# Wifi_Board.net
KiCad netlist of a schematic drawn in EAGLE
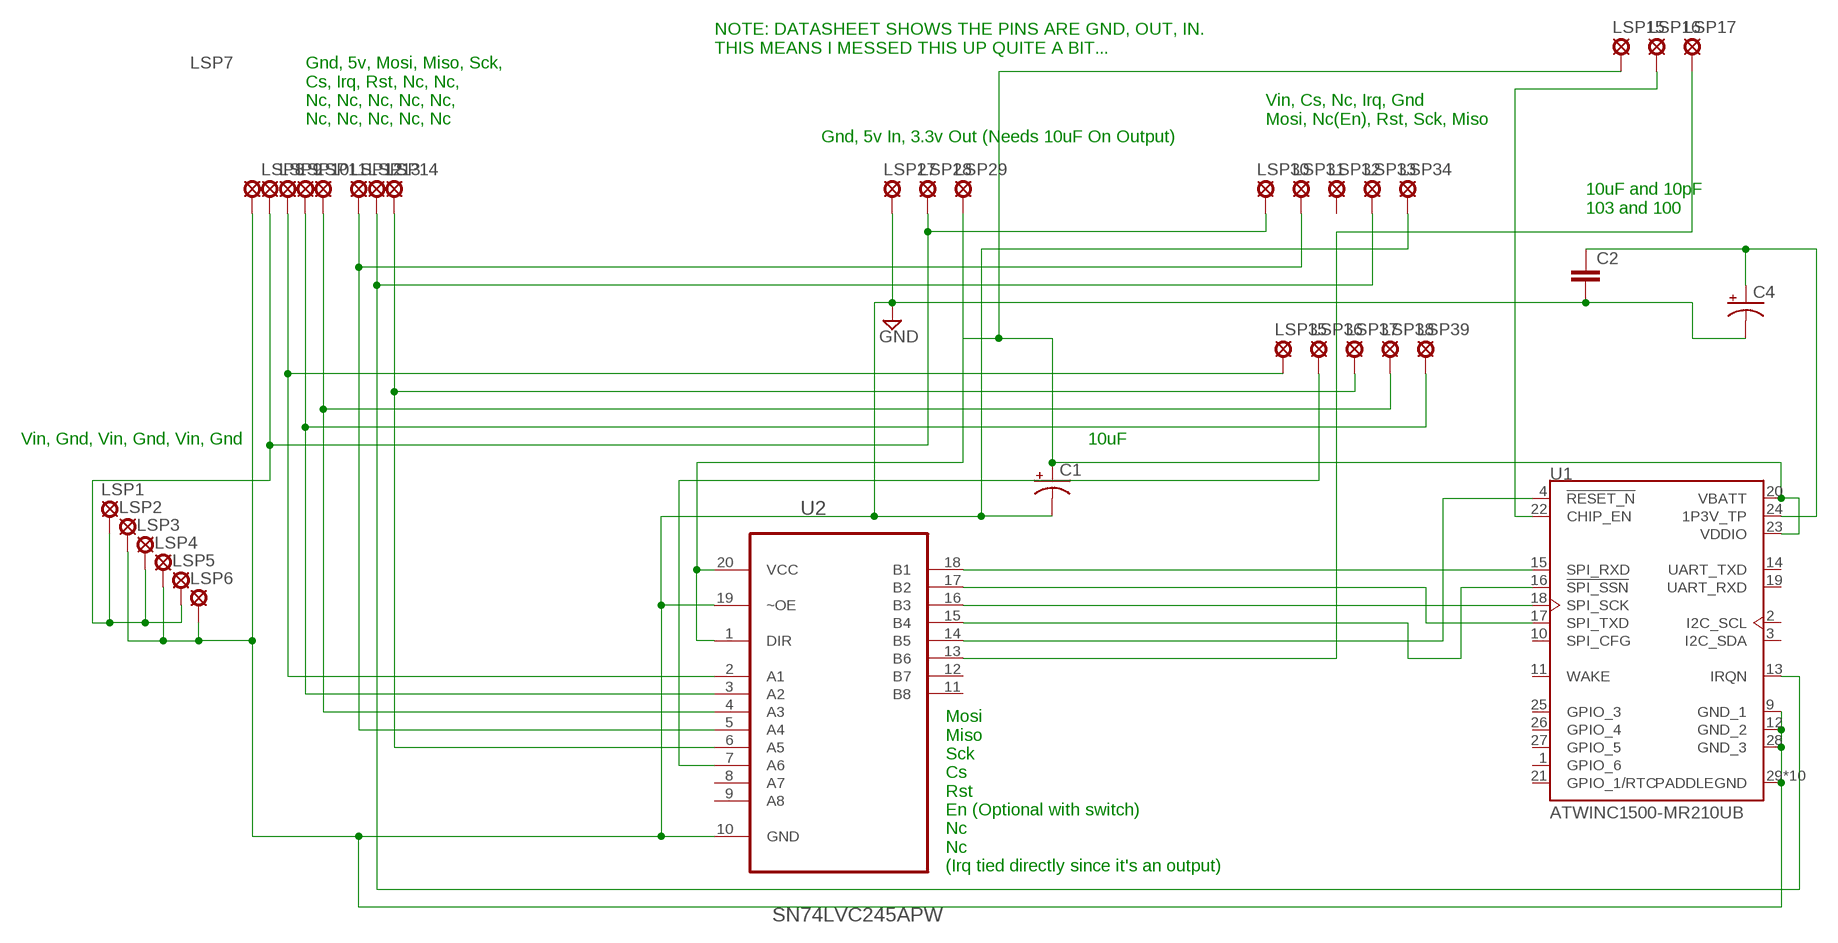
[diagram p0: schematic, sheet 1]

(export (version "E")
  (design (tool "Eeschema 10.0.6"))
  (components
    (comp (ref "C1")
      (value "CPOL-USE2-4")
      (footprint "eagle-import:E2-4")
      (libsource (lib "eagle-import") (part "CPOL-USE2-4"))
    )
    (comp (ref "C2")
      (value "C5/2.5")
      (footprint "eagle-import:C5B2.5")
      (libsource (lib "eagle-import") (part "C5/2.5"))
    )
    (comp (ref "C4")
      (value "CPOL-USE2-4")
      (footprint "eagle-import:E2-4")
      (libsource (lib "eagle-import") (part "CPOL-USE2-4"))
    )
    (comp (ref "LSP1")
      (value "LSP10_CLSP10_C")
      (footprint "eagle-import:LSP10_C")
      (libsource (lib "eagle-import") (part "LSP10_CLSP10_C"))
    )
    (comp (ref "LSP2")
      (value "LSP10_CLSP10_C")
      (footprint "eagle-import:LSP10_C")
      (libsource (lib "eagle-import") (part "LSP10_CLSP10_C"))
    )
    (comp (ref "LSP3")
      (value "LSP10_CLSP10_C")
      (footprint "eagle-import:LSP10_C")
      (libsource (lib "eagle-import") (part "LSP10_CLSP10_C"))
    )
    (comp (ref "LSP4")
      (value "LSP10_CLSP10_C")
      (footprint "eagle-import:LSP10_C")
      (libsource (lib "eagle-import") (part "LSP10_CLSP10_C"))
    )
    (comp (ref "LSP5")
      (value "LSP10_CLSP10_C")
      (footprint "eagle-import:LSP10_C")
      (libsource (lib "eagle-import") (part "LSP10_CLSP10_C"))
    )
    (comp (ref "LSP6")
      (value "LSP10_CLSP10_C")
      (footprint "eagle-import:LSP10_C")
      (libsource (lib "eagle-import") (part "LSP10_CLSP10_C"))
    )
    (comp (ref "LSP7")
      (value "LSP10_CLSP10_C")
      (footprint "eagle-import:LSP10_C")
      (libsource (lib "eagle-import") (part "LSP10_CLSP10_C"))
    )
    (comp (ref "LSP8")
      (value "LSP10_CLSP10_C")
      (footprint "eagle-import:LSP10_C")
      (libsource (lib "eagle-import") (part "LSP10_CLSP10_C"))
    )
    (comp (ref "LSP9")
      (value "LSP10_CLSP10_C")
      (footprint "eagle-import:LSP10_C")
      (libsource (lib "eagle-import") (part "LSP10_CLSP10_C"))
    )
    (comp (ref "LSP10")
      (value "LSP10_CLSP10_C")
      (footprint "eagle-import:LSP10_C")
      (libsource (lib "eagle-import") (part "LSP10_CLSP10_C"))
    )
    (comp (ref "LSP11")
      (value "LSP10_CLSP10_C")
      (footprint "eagle-import:LSP10_C")
      (libsource (lib "eagle-import") (part "LSP10_CLSP10_C"))
    )
    (comp (ref "LSP12")
      (value "LSP10_CLSP10_C")
      (footprint "eagle-import:LSP10_C")
      (libsource (lib "eagle-import") (part "LSP10_CLSP10_C"))
    )
    (comp (ref "LSP13")
      (value "LSP10_CLSP10_C")
      (footprint "eagle-import:LSP10_C")
      (libsource (lib "eagle-import") (part "LSP10_CLSP10_C"))
    )
    (comp (ref "LSP14")
      (value "LSP10_CLSP10_C")
      (footprint "eagle-import:LSP10_C")
      (libsource (lib "eagle-import") (part "LSP10_CLSP10_C"))
    )
    (comp (ref "LSP15")
      (value "LSP10_CLSP10_C")
      (footprint "eagle-import:LSP10_C")
      (libsource (lib "eagle-import") (part "LSP10_CLSP10_C"))
    )
    (comp (ref "LSP16")
      (value "LSP10_CLSP10_C")
      (footprint "eagle-import:LSP10_C")
      (libsource (lib "eagle-import") (part "LSP10_CLSP10_C"))
    )
    (comp (ref "LSP17")
      (value "LSP10_CLSP10_C")
      (footprint "eagle-import:LSP10_C")
      (libsource (lib "eagle-import") (part "LSP10_CLSP10_C"))
    )
    (comp (ref "LSP27")
      (value "LSP10_CLSP10_C")
      (footprint "eagle-import:LSP10_C")
      (libsource (lib "eagle-import") (part "LSP10_CLSP10_C"))
    )
    (comp (ref "LSP28")
      (value "LSP10_CLSP10_C")
      (footprint "eagle-import:LSP10_C")
      (libsource (lib "eagle-import") (part "LSP10_CLSP10_C"))
    )
    (comp (ref "LSP29")
      (value "LSP10_CLSP10_C")
      (footprint "eagle-import:LSP10_C")
      (libsource (lib "eagle-import") (part "LSP10_CLSP10_C"))
    )
    (comp (ref "LSP30")
      (value "LSP10_CLSP10_C")
      (footprint "eagle-import:LSP10_C")
      (libsource (lib "eagle-import") (part "LSP10_CLSP10_C"))
    )
    (comp (ref "LSP31")
      (value "LSP10_CLSP10_C")
      (footprint "eagle-import:LSP10_C")
      (libsource (lib "eagle-import") (part "LSP10_CLSP10_C"))
    )
    (comp (ref "LSP32")
      (value "LSP10_CLSP10_C")
      (footprint "eagle-import:LSP10_C")
      (libsource (lib "eagle-import") (part "LSP10_CLSP10_C"))
    )
    (comp (ref "LSP33")
      (value "LSP10_CLSP10_C")
      (footprint "eagle-import:LSP10_C")
      (libsource (lib "eagle-import") (part "LSP10_CLSP10_C"))
    )
    (comp (ref "LSP34")
      (value "LSP10_CLSP10_C")
      (footprint "eagle-import:LSP10_C")
      (libsource (lib "eagle-import") (part "LSP10_CLSP10_C"))
    )
    (comp (ref "LSP35")
      (value "LSP10_CLSP10_C")
      (footprint "eagle-import:LSP10_C")
      (libsource (lib "eagle-import") (part "LSP10_CLSP10_C"))
    )
    (comp (ref "LSP36")
      (value "LSP10_CLSP10_C")
      (footprint "eagle-import:LSP10_C")
      (libsource (lib "eagle-import") (part "LSP10_CLSP10_C"))
    )
    (comp (ref "LSP37")
      (value "LSP10_CLSP10_C")
      (footprint "eagle-import:LSP10_C")
      (libsource (lib "eagle-import") (part "LSP10_CLSP10_C"))
    )
    (comp (ref "LSP38")
      (value "LSP10_CLSP10_C")
      (footprint "eagle-import:LSP10_C")
      (libsource (lib "eagle-import") (part "LSP10_CLSP10_C"))
    )
    (comp (ref "LSP39")
      (value "LSP10_CLSP10_C")
      (footprint "eagle-import:LSP10_C")
      (libsource (lib "eagle-import") (part "LSP10_CLSP10_C"))
    )
    (comp (ref "U1")
      (value "ATWINC1500-MR210UB")
      (footprint "eagle-import:MICROCHIP_ATWINC1500-MR210UB")
      (fields (field (name "MF") "Microchip"))
      (libsource (lib "eagle-import") (part "ATWINC1500-MR210UB"))
    )
    (comp (ref "U2")
      (value "SN74LVC245APW")
      (footprint "eagle-import:SOP65P640X120-20N")
      (fields (field (name "MF") "Texas Instruments"))
      (libsource (lib "eagle-import") (part "SN74LVC245APW"))
    )
  )
  (nets
    (net (code "1") (name "GND") (class "Default")
      (node (ref "C1") (pin "-") (pinfunction "-_-") (pintype "passive"))
      (node (ref "C2") (pin "2") (pinfunction "2_2") (pintype "passive"))
      (node (ref "C4") (pin "-") (pinfunction "-_-") (pintype "passive"))
      (node (ref "LSP2") (pin "P$1") (pinfunction "MP_P$1") (pintype "passive"))
      (node (ref "LSP27") (pin "P$1") (pinfunction "MP_P$1") (pintype "passive"))
      (node (ref "LSP34") (pin "P$1") (pinfunction "MP_P$1") (pintype "passive"))
      (node (ref "LSP4") (pin "P$1") (pinfunction "MP_P$1") (pintype "passive"))
      (node (ref "LSP6") (pin "P$1") (pinfunction "MP_P$1") (pintype "passive"))
      (node (ref "LSP7") (pin "P$1") (pinfunction "MP_P$1") (pintype "passive"))
      (node (ref "U1") (pin "12") (pinfunction "GND_2_12") (pintype "power_in"))
      (node (ref "U1") (pin "28") (pinfunction "GND_3_28") (pintype "power_in"))
      (node (ref "U1") (pin "29") (pinfunction "PADDLEGND_29") (pintype "power_in"))
      (node (ref "U1") (pin "9") (pinfunction "GND_1_9") (pintype "power_in"))
      (node (ref "U1") (pin "P$1") (pinfunction "PADDLEGND_P$1") (pintype "power_in"))
      (node (ref "U1") (pin "P$2") (pinfunction "PADDLEGND_P$2") (pintype "power_in"))
      (node (ref "U1") (pin "P$3") (pinfunction "PADDLEGND_P$3") (pintype "power_in"))
      (node (ref "U1") (pin "P$4") (pinfunction "PADDLEGND_P$4") (pintype "power_in"))
      (node (ref "U1") (pin "P$5") (pinfunction "PADDLEGND_P$5") (pintype "power_in"))
      (node (ref "U1") (pin "P$6") (pinfunction "PADDLEGND_P$6") (pintype "power_in"))
      (node (ref "U1") (pin "P$7") (pinfunction "PADDLEGND_P$7") (pintype "power_in"))
      (node (ref "U1") (pin "P$8") (pinfunction "PADDLEGND_P$8") (pintype "power_in"))
      (node (ref "U1") (pin "P$9") (pinfunction "PADDLEGND_P$9") (pintype "power_in"))
      (node (ref "U2") (pin "10") (pinfunction "GND_10") (pintype "passive"))
      (node (ref "U2") (pin "19") (pinfunction "~{OE}_19") (pintype "input"))
    )
    (net (code "2") (name "Net-(LSP1-MP)") (class "Default")
      (node (ref "LSP1") (pin "P$1") (pinfunction "MP_P$1") (pintype "passive"))
      (node (ref "LSP28") (pin "P$1") (pinfunction "MP_P$1") (pintype "passive"))
      (node (ref "LSP3") (pin "P$1") (pinfunction "MP_P$1") (pintype "passive"))
      (node (ref "LSP30") (pin "P$1") (pinfunction "MP_P$1") (pintype "passive"))
      (node (ref "LSP5") (pin "P$1") (pinfunction "MP_P$1") (pintype "passive"))
      (node (ref "LSP8") (pin "P$1") (pinfunction "MP_P$1") (pintype "passive"))
    )
    (net (code "3") (name "Net-(LSP10-MP)") (class "Default")
      (node (ref "LSP10") (pin "P$1") (pinfunction "MP_P$1") (pintype "passive"))
      (node (ref "LSP39") (pin "P$1") (pinfunction "MP_P$1") (pintype "passive"))
      (node (ref "U2") (pin "3") (pinfunction "A2_3") (pintype "bidirectional"))
    )
    (net (code "4") (name "Net-(LSP11-MP)") (class "Default")
      (node (ref "LSP11") (pin "P$1") (pinfunction "MP_P$1") (pintype "passive"))
      (node (ref "LSP38") (pin "P$1") (pinfunction "MP_P$1") (pintype "passive"))
      (node (ref "U2") (pin "4") (pinfunction "A3_4") (pintype "bidirectional"))
    )
    (net (code "5") (name "Net-(LSP12-MP)") (class "Default")
      (node (ref "LSP12") (pin "P$1") (pinfunction "MP_P$1") (pintype "passive"))
      (node (ref "LSP31") (pin "P$1") (pinfunction "MP_P$1") (pintype "passive"))
      (node (ref "U2") (pin "5") (pinfunction "A4_5") (pintype "bidirectional"))
    )
    (net (code "6") (name "Net-(LSP13-MP)") (class "Default")
      (node (ref "LSP13") (pin "P$1") (pinfunction "MP_P$1") (pintype "passive"))
      (node (ref "LSP33") (pin "P$1") (pinfunction "MP_P$1") (pintype "passive"))
      (node (ref "U1") (pin "13") (pinfunction "IRQN_13") (pintype "output"))
    )
    (net (code "7") (name "Net-(LSP14-MP)") (class "Default")
      (node (ref "LSP14") (pin "P$1") (pinfunction "MP_P$1") (pintype "passive"))
      (node (ref "LSP37") (pin "P$1") (pinfunction "MP_P$1") (pintype "passive"))
      (node (ref "U2") (pin "6") (pinfunction "A5_6") (pintype "bidirectional"))
    )
    (net (code "8") (name "Net-(LSP15-MP)") (class "Default")
      (node (ref "C1") (pin "+") (pinfunction "+_+") (pintype "passive"))
      (node (ref "LSP15") (pin "P$1") (pinfunction "MP_P$1") (pintype "passive"))
      (node (ref "LSP29") (pin "P$1") (pinfunction "MP_P$1") (pintype "passive"))
      (node (ref "U1") (pin "20") (pinfunction "VBATT_20") (pintype "power_in"))
      (node (ref "U1") (pin "23") (pinfunction "VDDIO_23") (pintype "power_in"))
      (node (ref "U2") (pin "1") (pinfunction "DIR_1") (pintype "input"))
      (node (ref "U2") (pin "20") (pinfunction "VCC_20") (pintype "power_in"))
    )
    (net (code "9") (name "Net-(LSP16-MP)") (class "Default")
      (node (ref "LSP16") (pin "P$1") (pinfunction "MP_P$1") (pintype "passive"))
      (node (ref "U1") (pin "22") (pinfunction "CHIP_EN_22") (pintype "input"))
    )
    (net (code "10") (name "Net-(LSP17-MP)") (class "Default")
      (node (ref "LSP17") (pin "P$1") (pinfunction "MP_P$1") (pintype "passive"))
      (node (ref "U2") (pin "13") (pinfunction "B6_13") (pintype "bidirectional"))
    )
    (net (code "11") (name "Net-(LSP35-MP)") (class "Default")
      (node (ref "LSP35") (pin "P$1") (pinfunction "MP_P$1") (pintype "passive"))
      (node (ref "LSP9") (pin "P$1") (pinfunction "MP_P$1") (pintype "passive"))
      (node (ref "U2") (pin "2") (pinfunction "A1_2") (pintype "bidirectional"))
    )
    (net (code "12") (name "Net-(LSP36-MP)") (class "Default")
      (node (ref "LSP36") (pin "P$1") (pinfunction "MP_P$1") (pintype "passive"))
      (node (ref "U2") (pin "7") (pinfunction "A6_7") (pintype "bidirectional"))
    )
    (net (code "13") (name "Net-(U1-1P3V_TP)") (class "Default")
      (node (ref "C2") (pin "1") (pinfunction "1_1") (pintype "passive"))
      (node (ref "C4") (pin "+") (pinfunction "+_+") (pintype "passive"))
      (node (ref "U1") (pin "24") (pinfunction "1P3V_TP_24") (pintype "power_in"))
    )
    (net (code "14") (name "Net-(U1-SPI_RXD)") (class "Default")
      (node (ref "U1") (pin "15") (pinfunction "SPI_RXD_15") (pintype "input"))
      (node (ref "U2") (pin "18") (pinfunction "B1_18") (pintype "bidirectional"))
    )
    (net (code "15") (name "Net-(U1-SPI_SCK)") (class "Default")
      (node (ref "U1") (pin "18") (pinfunction "SPI_SCK_18") (pintype "input"))
      (node (ref "U2") (pin "16") (pinfunction "B3_16") (pintype "bidirectional"))
    )
    (net (code "16") (name "Net-(U1-SPI_TXD)") (class "Default")
      (node (ref "U1") (pin "17") (pinfunction "SPI_TXD_17") (pintype "output"))
      (node (ref "U2") (pin "17") (pinfunction "B2_17") (pintype "bidirectional"))
    )
    (net (code "17") (name "Net-(U1-~{RESET_N})") (class "Default")
      (node (ref "U1") (pin "4") (pinfunction "~{RESET_N}_4") (pintype "input"))
      (node (ref "U2") (pin "14") (pinfunction "B5_14") (pintype "bidirectional"))
    )
    (net (code "18") (name "Net-(U1-~{SPI_SSN})") (class "Default")
      (node (ref "U1") (pin "16") (pinfunction "~{SPI_SSN}_16") (pintype "input"))
      (node (ref "U2") (pin "15") (pinfunction "B4_15") (pintype "bidirectional"))
    )
    (net (code "19") (name "unconnected-(LSP32-MP-PadP$1)") (class "Default")
      (node (ref "LSP32") (pin "P$1") (pinfunction "MP_P$1") (pintype "passive"))
    )
    (net (code "20") (name "unconnected-(U1-GPIO_1{slash}RTC-Pad21)") (class "Default")
      (node (ref "U1") (pin "21") (pinfunction "GPIO_1/RTC_21") (pintype "input"))
    )
    (net (code "21") (name "unconnected-(U1-GPIO_3-Pad25)") (class "Default")
      (node (ref "U1") (pin "25") (pinfunction "GPIO_3_25") (pintype "bidirectional"))
    )
    (net (code "22") (name "unconnected-(U1-GPIO_4-Pad26)") (class "Default")
      (node (ref "U1") (pin "26") (pinfunction "GPIO_4_26") (pintype "bidirectional"))
    )
    (net (code "23") (name "unconnected-(U1-GPIO_5-Pad27)") (class "Default")
      (node (ref "U1") (pin "27") (pinfunction "GPIO_5_27") (pintype "bidirectional"))
    )
    (net (code "24") (name "unconnected-(U1-GPIO_6-Pad1)") (class "Default")
      (node (ref "U1") (pin "1") (pinfunction "GPIO_6_1") (pintype "bidirectional"))
    )
    (net (code "25") (name "unconnected-(U1-I2C_SCL-Pad2)") (class "Default")
      (node (ref "U1") (pin "2") (pinfunction "I2C_SCL_2") (pintype "bidirectional"))
    )
    (net (code "26") (name "unconnected-(U1-I2C_SDA-Pad3)") (class "Default")
      (node (ref "U1") (pin "3") (pinfunction "I2C_SDA_3") (pintype "bidirectional"))
    )
    (net (code "27") (name "unconnected-(U1-SPI_CFG-Pad10)") (class "Default")
      (node (ref "U1") (pin "10") (pinfunction "SPI_CFG_10") (pintype "input"))
    )
    (net (code "28") (name "unconnected-(U1-UART_RXD-Pad19)") (class "Default")
      (node (ref "U1") (pin "19") (pinfunction "UART_RXD_19") (pintype "input"))
    )
    (net (code "29") (name "unconnected-(U1-UART_TXD-Pad14)") (class "Default")
      (node (ref "U1") (pin "14") (pinfunction "UART_TXD_14") (pintype "output"))
    )
    (net (code "30") (name "unconnected-(U1-WAKE-Pad11)") (class "Default")
      (node (ref "U1") (pin "11") (pinfunction "WAKE_11") (pintype "input"))
    )
    (net (code "31") (name "unconnected-(U2-A7-Pad8)") (class "Default")
      (node (ref "U2") (pin "8") (pinfunction "A7_8") (pintype "bidirectional"))
    )
    (net (code "32") (name "unconnected-(U2-A8-Pad9)") (class "Default")
      (node (ref "U2") (pin "9") (pinfunction "A8_9") (pintype "bidirectional"))
    )
    (net (code "33") (name "unconnected-(U2-B7-Pad12)") (class "Default")
      (node (ref "U2") (pin "12") (pinfunction "B7_12") (pintype "bidirectional"))
    )
    (net (code "34") (name "unconnected-(U2-B8-Pad11)") (class "Default")
      (node (ref "U2") (pin "11") (pinfunction "B8_11") (pintype "bidirectional"))
    )
  )
)
